# Connectors.net
KiCad netlist of a schematic drawn in Altium Designer
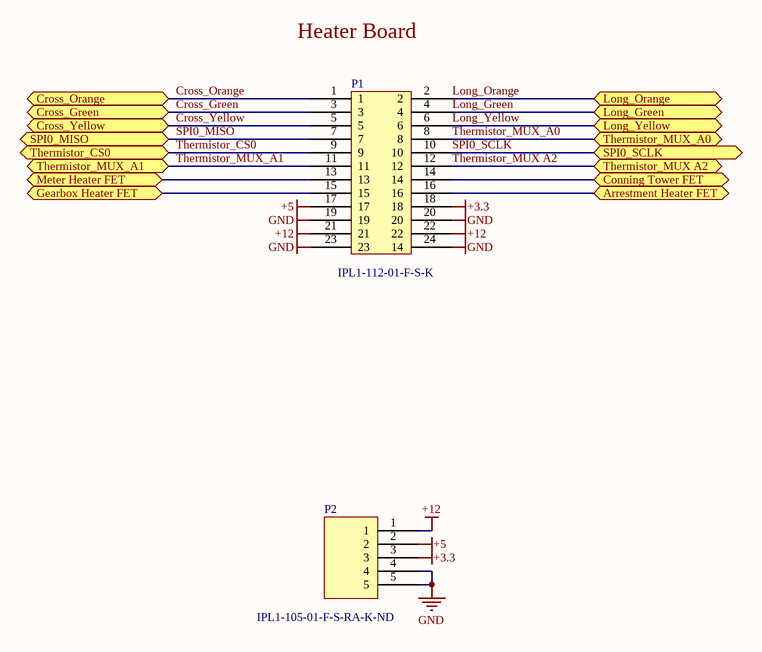
[diagram p0: Connectors.SchDoc]

(export (version "E")
  (design (tool "Eeschema 10.0.6"))
  (components
    (comp (ref "P1")
      (value "IPL1-112-01-F-S-K")
      (footprint "IPL1-112-01-F-S-K")
      (description "IPL1-112-01-F-D-K")
      (fields
        (field (name "SUPPLIER PART NUMBER 2") "IPL1-112-01-F-S-K")
        (field (name "MANUFACTURER") "Samtec")
      )
      (libsource (lib "ZLS_Schematic_lib") (part "IPL1-112-01-F-S-K"))
    )
    (comp (ref "P2")
      (value "IPL1-105-01-F-S-RA")
      (footprint "IPL1-105-01-F-S-RA")
      (fields (field (name "SUPPLIER PART NUMBER 1") "IPL1-105-01-F-S-RA-K-ND"))
      (libsource (lib "ZLS_Schematic_lib") (part "IPL1-105-01-F-S-RA"))
    )
  )
  (nets
    (net (code "1") (name "+3.3") (class "Default")
      (node (ref "P1") (pin "18") (pinfunction "18_18") (pintype "passive"))
      (node (ref "P2") (pin "3") (pinfunction "3_3") (pintype "passive"))
    )
    (net (code "2") (name "+5") (class "Default")
      (node (ref "P1") (pin "17") (pinfunction "17_17") (pintype "passive"))
      (node (ref "P2") (pin "2") (pinfunction "2_2") (pintype "passive"))
    )
    (net (code "3") (name "+12") (class "Default")
      (node (ref "P1") (pin "21") (pinfunction "21_21") (pintype "passive"))
      (node (ref "P1") (pin "22") (pinfunction "22_22") (pintype "passive"))
      (node (ref "P2") (pin "1") (pinfunction "1_1") (pintype "passive"))
    )
    (net (code "4") (name "/Arrestment Heater FET") (class "Default")
      (node (ref "P1") (pin "16") (pinfunction "16_16") (pintype "passive"))
    )
    (net (code "5") (name "/Conning Tower FET") (class "Default")
      (node (ref "P1") (pin "14") (pinfunction "14_14") (pintype "passive"))
    )
    (net (code "6") (name "/Cross_Green") (class "Default")
      (node (ref "P1") (pin "3") (pinfunction "3_3") (pintype "passive"))
    )
    (net (code "7") (name "/Cross_Orange") (class "Default")
      (node (ref "P1") (pin "1") (pinfunction "1_1") (pintype "passive"))
    )
    (net (code "8") (name "/Cross_Yellow") (class "Default")
      (node (ref "P1") (pin "5") (pinfunction "5_5") (pintype "passive"))
    )
    (net (code "9") (name "/Gearbox Heater FET") (class "Default")
      (node (ref "P1") (pin "15") (pinfunction "15_15") (pintype "passive"))
    )
    (net (code "10") (name "/Long_Green") (class "Default")
      (node (ref "P1") (pin "4") (pinfunction "4_4") (pintype "passive"))
    )
    (net (code "11") (name "/Long_Orange") (class "Default")
      (node (ref "P1") (pin "2") (pinfunction "2_2") (pintype "passive"))
    )
    (net (code "12") (name "/Long_Yellow") (class "Default")
      (node (ref "P1") (pin "6") (pinfunction "6_6") (pintype "passive"))
    )
    (net (code "13") (name "/Meter Heater FET") (class "Default")
      (node (ref "P1") (pin "13") (pinfunction "13_13") (pintype "passive"))
    )
    (net (code "14") (name "/SPI0_MISO") (class "Default")
      (node (ref "P1") (pin "7") (pinfunction "7_7") (pintype "passive"))
    )
    (net (code "15") (name "/SPI0_SCLK") (class "Default")
      (node (ref "P1") (pin "10") (pinfunction "10_10") (pintype "passive"))
    )
    (net (code "16") (name "/Thermistor_CS0") (class "Default")
      (node (ref "P1") (pin "9") (pinfunction "9_9") (pintype "passive"))
    )
    (net (code "17") (name "/Thermistor_MUX A2") (class "Default")
      (node (ref "P1") (pin "12") (pinfunction "12_12") (pintype "passive"))
    )
    (net (code "18") (name "/Thermistor_MUX_A0") (class "Default")
      (node (ref "P1") (pin "8") (pinfunction "8_8") (pintype "passive"))
    )
    (net (code "19") (name "/Thermistor_MUX_A1") (class "Default")
      (node (ref "P1") (pin "11") (pinfunction "11_11") (pintype "passive"))
    )
    (net (code "20") (name "GND") (class "Default")
      (node (ref "P1") (pin "19") (pinfunction "19_19") (pintype "passive"))
      (node (ref "P1") (pin "20") (pinfunction "20_20") (pintype "passive"))
      (node (ref "P1") (pin "23") (pinfunction "23_23") (pintype "passive"))
      (node (ref "P1") (pin "24") (pinfunction "14_24") (pintype "passive"))
      (node (ref "P2") (pin "4") (pinfunction "4_4") (pintype "passive"))
      (node (ref "P2") (pin "5") (pinfunction "5_5") (pintype "passive"))
    )
  )
)
